# mcp23017_L298.net
KiCad netlist of a schematic drawn in EAGLE
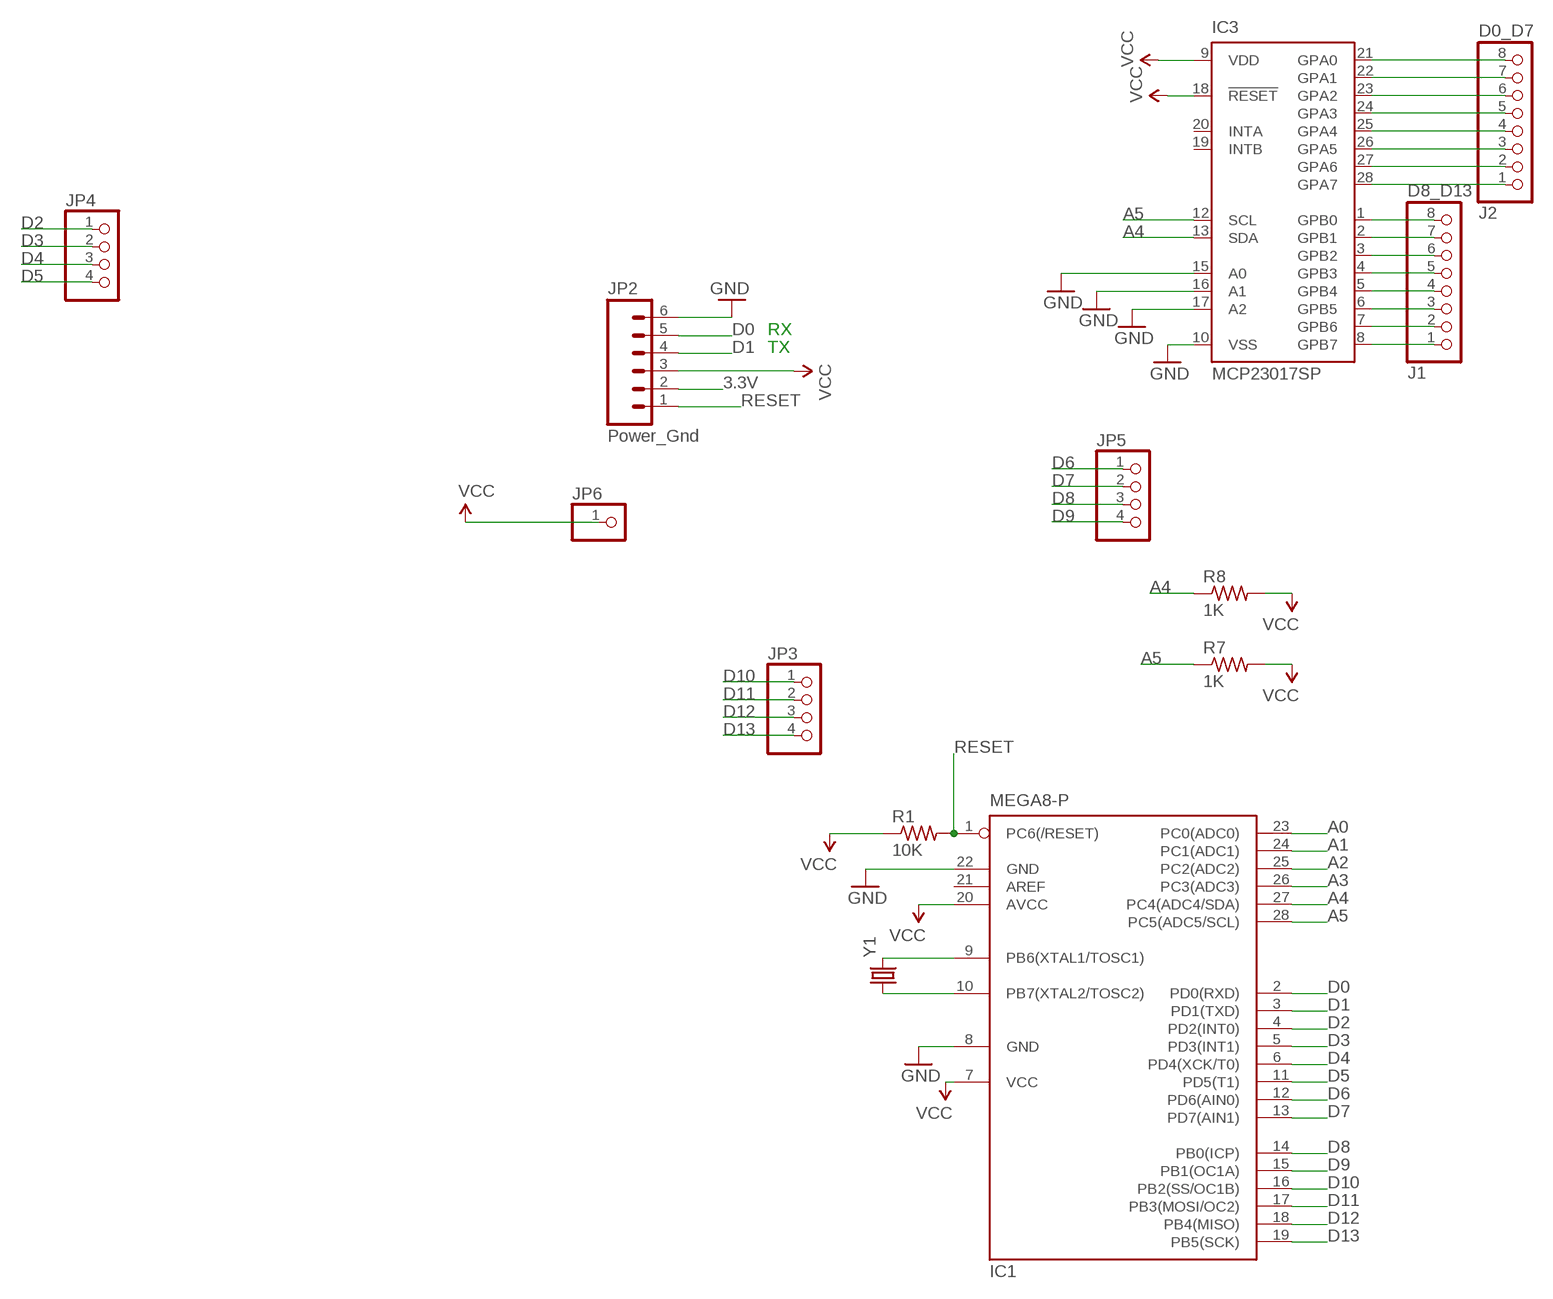
[diagram p0: schematic, sheet 1]

(export (version "E")
  (design (tool "Eeschema 10.0.6"))
  (components
    (comp (ref "IC1")
      (value "MEGA8-P")
      (footprint "eagle-import:DIL28-3")
      (libsource (lib "eagle-import") (part "MEGA8-P"))
    )
    (comp (ref "IC3")
      (value "MCP23017SP")
      (footprint "eagle-import:DIL28-3")
      (fields (field (name "MF") "MICROCHIP") (field (name "MPN") "MCP23017-E/SP"))
      (libsource (lib "eagle-import") (part "MCP23017SP"))
    )
    (comp (ref "J1")
      (value "D8_D13")
      (footprint "eagle-import:1X08")
      (libsource (lib "eagle-import") (part "PINHD-1X8"))
    )
    (comp (ref "J2")
      (value "D0_D7")
      (footprint "eagle-import:1X08")
      (libsource (lib "eagle-import") (part "PINHD-1X8"))
    )
    (comp (ref "JP2")
      (value "Power_Gnd")
      (footprint "eagle-import:1X06")
      (libsource (lib "eagle-import") (part "M06SIP"))
    )
    (comp (ref "JP3")
      (value "PINHD-1X4")
      (footprint "eagle-import:1X04")
      (libsource (lib "eagle-import") (part "PINHD-1X4"))
    )
    (comp (ref "JP4")
      (value "PINHD-1X4")
      (footprint "eagle-import:1X04")
      (libsource (lib "eagle-import") (part "PINHD-1X4"))
    )
    (comp (ref "JP5")
      (value "PINHD-1X4")
      (footprint "eagle-import:1X04")
      (libsource (lib "eagle-import") (part "PINHD-1X4"))
    )
    (comp (ref "JP6")
      (value "PINHD-1X1")
      (footprint "eagle-import:1X01")
      (libsource (lib "eagle-import") (part "PINHD-1X1"))
    )
    (comp (ref "R1")
      (value "10K")
      (footprint "eagle-import:0207_10")
      (libsource (lib "eagle-import") (part "R-US_0207/10"))
    )
    (comp (ref "R7")
      (value "1K")
      (footprint "eagle-import:0207_10")
      (libsource (lib "eagle-import") (part "R-US_0207/10"))
    )
    (comp (ref "R8")
      (value "1K")
      (footprint "eagle-import:0207_10")
      (libsource (lib "eagle-import") (part "R-US_0207/10"))
    )
    (comp (ref "Y1")
      (value "CRYSTALHC49US")
      (footprint "eagle-import:HC49US")
      (libsource (lib "eagle-import") (part "CRYSTALHC49US"))
    )
  )
  (nets
    (net (code "1") (name "/3.3V") (class "Default")
      (node (ref "JP2") (pin "2") (pinfunction "2_2") (pintype "passive"))
    )
    (net (code "2") (name "/A0") (class "Default")
      (node (ref "IC1") (pin "23") (pinfunction "PC0(ADC0)_23") (pintype "bidirectional"))
    )
    (net (code "3") (name "/A1") (class "Default")
      (node (ref "IC1") (pin "24") (pinfunction "PC1(ADC1)_24") (pintype "bidirectional"))
    )
    (net (code "4") (name "/A2") (class "Default")
      (node (ref "IC1") (pin "25") (pinfunction "PC2(ADC2)_25") (pintype "bidirectional"))
    )
    (net (code "5") (name "/A3") (class "Default")
      (node (ref "IC1") (pin "26") (pinfunction "PC3(ADC3)_26") (pintype "bidirectional"))
    )
    (net (code "6") (name "/A4") (class "Default")
      (node (ref "IC1") (pin "27") (pinfunction "PC4(ADC4/SDA)_27") (pintype "bidirectional"))
      (node (ref "IC3") (pin "13") (pinfunction "SDA_13") (pintype "bidirectional"))
      (node (ref "R8") (pin "1") (pinfunction "1_1") (pintype "passive"))
    )
    (net (code "7") (name "/A5") (class "Default")
      (node (ref "IC1") (pin "28") (pinfunction "PC5(ADC5/SCL)_28") (pintype "bidirectional"))
      (node (ref "IC3") (pin "12") (pinfunction "SCL_12") (pintype "input"))
      (node (ref "R7") (pin "1") (pinfunction "1_1") (pintype "passive"))
    )
    (net (code "8") (name "/D0") (class "Default")
      (node (ref "IC1") (pin "2") (pinfunction "PD0(RXD)_2") (pintype "bidirectional"))
      (node (ref "JP2") (pin "5") (pinfunction "5_5") (pintype "passive"))
    )
    (net (code "9") (name "/D1") (class "Default")
      (node (ref "IC1") (pin "3") (pinfunction "PD1(TXD)_3") (pintype "bidirectional"))
      (node (ref "JP2") (pin "4") (pinfunction "4_4") (pintype "passive"))
    )
    (net (code "10") (name "/D2") (class "Default")
      (node (ref "IC1") (pin "4") (pinfunction "PD2(INT0)_4") (pintype "bidirectional"))
      (node (ref "JP4") (pin "1") (pinfunction "1_1") (pintype "passive"))
    )
    (net (code "11") (name "/D3") (class "Default")
      (node (ref "IC1") (pin "5") (pinfunction "PD3(INT1)_5") (pintype "bidirectional"))
      (node (ref "JP4") (pin "2") (pinfunction "2_2") (pintype "passive"))
    )
    (net (code "12") (name "/D4") (class "Default")
      (node (ref "IC1") (pin "6") (pinfunction "PD4(XCK/T0)_6") (pintype "bidirectional"))
      (node (ref "JP4") (pin "3") (pinfunction "3_3") (pintype "passive"))
    )
    (net (code "13") (name "/D5") (class "Default")
      (node (ref "IC1") (pin "11") (pinfunction "PD5(T1)_11") (pintype "bidirectional"))
      (node (ref "JP4") (pin "4") (pinfunction "4_4") (pintype "passive"))
    )
    (net (code "14") (name "/D6") (class "Default")
      (node (ref "IC1") (pin "12") (pinfunction "PD6(AIN0)_12") (pintype "bidirectional"))
      (node (ref "JP5") (pin "1") (pinfunction "1_1") (pintype "passive"))
    )
    (net (code "15") (name "/D7") (class "Default")
      (node (ref "IC1") (pin "13") (pinfunction "PD7(AIN1)_13") (pintype "bidirectional"))
      (node (ref "JP5") (pin "2") (pinfunction "2_2") (pintype "passive"))
    )
    (net (code "16") (name "/D8") (class "Default")
      (node (ref "IC1") (pin "14") (pinfunction "PB0(ICP)_14") (pintype "bidirectional"))
      (node (ref "JP5") (pin "3") (pinfunction "3_3") (pintype "passive"))
    )
    (net (code "17") (name "/D9") (class "Default")
      (node (ref "IC1") (pin "15") (pinfunction "PB1(OC1A)_15") (pintype "bidirectional"))
      (node (ref "JP5") (pin "4") (pinfunction "4_4") (pintype "passive"))
    )
    (net (code "18") (name "/D10") (class "Default")
      (node (ref "IC1") (pin "16") (pinfunction "PB2(SS/OC1B)_16") (pintype "bidirectional"))
      (node (ref "JP3") (pin "1") (pinfunction "1_1") (pintype "passive"))
    )
    (net (code "19") (name "/D11") (class "Default")
      (node (ref "IC1") (pin "17") (pinfunction "PB3(MOSI/OC2)_17") (pintype "bidirectional"))
      (node (ref "JP3") (pin "2") (pinfunction "2_2") (pintype "passive"))
    )
    (net (code "20") (name "/D12") (class "Default")
      (node (ref "IC1") (pin "18") (pinfunction "PB4(MISO)_18") (pintype "bidirectional"))
      (node (ref "JP3") (pin "3") (pinfunction "3_3") (pintype "passive"))
    )
    (net (code "21") (name "/D13") (class "Default")
      (node (ref "IC1") (pin "19") (pinfunction "PB5(SCK)_19") (pintype "bidirectional"))
      (node (ref "JP3") (pin "4") (pinfunction "4_4") (pintype "passive"))
    )
    (net (code "22") (name "/RESET") (class "Default")
      (node (ref "IC1") (pin "1") (pinfunction "PC6(/RESET)_1") (pintype "bidirectional"))
      (node (ref "JP2") (pin "1") (pinfunction "1_1") (pintype "passive"))
      (node (ref "R1") (pin "2") (pinfunction "2_2") (pintype "passive"))
    )
    (net (code "23") (name "GND") (class "Default")
      (node (ref "IC1") (pin "22") (pinfunction "GND_22") (pintype "power_in"))
      (node (ref "IC1") (pin "8") (pinfunction "GND_8") (pintype "power_in"))
      (node (ref "IC3") (pin "10") (pinfunction "VSS_10") (pintype "power_in"))
      (node (ref "IC3") (pin "15") (pinfunction "A0_15") (pintype "input"))
      (node (ref "IC3") (pin "16") (pinfunction "A1_16") (pintype "input"))
      (node (ref "IC3") (pin "17") (pinfunction "A2_17") (pintype "input"))
      (node (ref "JP2") (pin "6") (pinfunction "6_6") (pintype "passive"))
    )
    (net (code "24") (name "Net-(IC1-PB6(XTAL1{slash}TOSC1))") (class "Default")
      (node (ref "IC1") (pin "9") (pinfunction "PB6(XTAL1/TOSC1)_9") (pintype "bidirectional"))
      (node (ref "Y1") (pin "2") (pinfunction "2_2") (pintype "passive"))
    )
    (net (code "25") (name "Net-(IC1-PB7(XTAL2{slash}TOSC2))") (class "Default")
      (node (ref "IC1") (pin "10") (pinfunction "PB7(XTAL2/TOSC2)_10") (pintype "bidirectional"))
      (node (ref "Y1") (pin "1") (pinfunction "1_1") (pintype "passive"))
    )
    (net (code "26") (name "Net-(IC3-GPA0)") (class "Default")
      (node (ref "IC3") (pin "21") (pinfunction "GPA0_21") (pintype "bidirectional"))
      (node (ref "J2") (pin "8") (pinfunction "8_8") (pintype "passive"))
    )
    (net (code "27") (name "Net-(IC3-GPA1)") (class "Default")
      (node (ref "IC3") (pin "22") (pinfunction "GPA1_22") (pintype "bidirectional"))
      (node (ref "J2") (pin "7") (pinfunction "7_7") (pintype "passive"))
    )
    (net (code "28") (name "Net-(IC3-GPA2)") (class "Default")
      (node (ref "IC3") (pin "23") (pinfunction "GPA2_23") (pintype "bidirectional"))
      (node (ref "J2") (pin "6") (pinfunction "6_6") (pintype "passive"))
    )
    (net (code "29") (name "Net-(IC3-GPA3)") (class "Default")
      (node (ref "IC3") (pin "24") (pinfunction "GPA3_24") (pintype "bidirectional"))
      (node (ref "J2") (pin "5") (pinfunction "5_5") (pintype "passive"))
    )
    (net (code "30") (name "Net-(IC3-GPA4)") (class "Default")
      (node (ref "IC3") (pin "25") (pinfunction "GPA4_25") (pintype "bidirectional"))
      (node (ref "J2") (pin "4") (pinfunction "4_4") (pintype "passive"))
    )
    (net (code "31") (name "Net-(IC3-GPA5)") (class "Default")
      (node (ref "IC3") (pin "26") (pinfunction "GPA5_26") (pintype "bidirectional"))
      (node (ref "J2") (pin "3") (pinfunction "3_3") (pintype "passive"))
    )
    (net (code "32") (name "Net-(IC3-GPA6)") (class "Default")
      (node (ref "IC3") (pin "27") (pinfunction "GPA6_27") (pintype "bidirectional"))
      (node (ref "J2") (pin "2") (pinfunction "2_2") (pintype "passive"))
    )
    (net (code "33") (name "Net-(IC3-GPA7)") (class "Default")
      (node (ref "IC3") (pin "28") (pinfunction "GPA7_28") (pintype "bidirectional"))
      (node (ref "J2") (pin "1") (pinfunction "1_1") (pintype "passive"))
    )
    (net (code "34") (name "Net-(IC3-GPB0)") (class "Default")
      (node (ref "IC3") (pin "1") (pinfunction "GPB0_1") (pintype "bidirectional"))
      (node (ref "J1") (pin "8") (pinfunction "8_8") (pintype "passive"))
    )
    (net (code "35") (name "Net-(IC3-GPB1)") (class "Default")
      (node (ref "IC3") (pin "2") (pinfunction "GPB1_2") (pintype "bidirectional"))
      (node (ref "J1") (pin "7") (pinfunction "7_7") (pintype "passive"))
    )
    (net (code "36") (name "Net-(IC3-GPB2)") (class "Default")
      (node (ref "IC3") (pin "3") (pinfunction "GPB2_3") (pintype "bidirectional"))
      (node (ref "J1") (pin "6") (pinfunction "6_6") (pintype "passive"))
    )
    (net (code "37") (name "Net-(IC3-GPB3)") (class "Default")
      (node (ref "IC3") (pin "4") (pinfunction "GPB3_4") (pintype "bidirectional"))
      (node (ref "J1") (pin "5") (pinfunction "5_5") (pintype "passive"))
    )
    (net (code "38") (name "Net-(IC3-GPB4)") (class "Default")
      (node (ref "IC3") (pin "5") (pinfunction "GPB4_5") (pintype "bidirectional"))
      (node (ref "J1") (pin "4") (pinfunction "4_4") (pintype "passive"))
    )
    (net (code "39") (name "Net-(IC3-GPB5)") (class "Default")
      (node (ref "IC3") (pin "6") (pinfunction "GPB5_6") (pintype "bidirectional"))
      (node (ref "J1") (pin "3") (pinfunction "3_3") (pintype "passive"))
    )
    (net (code "40") (name "Net-(IC3-GPB6)") (class "Default")
      (node (ref "IC3") (pin "7") (pinfunction "GPB6_7") (pintype "bidirectional"))
      (node (ref "J1") (pin "2") (pinfunction "2_2") (pintype "passive"))
    )
    (net (code "41") (name "Net-(IC3-GPB7)") (class "Default")
      (node (ref "IC3") (pin "8") (pinfunction "GPB7_8") (pintype "bidirectional"))
      (node (ref "J1") (pin "1") (pinfunction "1_1") (pintype "passive"))
    )
    (net (code "42") (name "VCC") (class "Default")
      (node (ref "IC1") (pin "20") (pinfunction "AVCC_20") (pintype "power_in"))
      (node (ref "IC1") (pin "7") (pinfunction "VCC_7") (pintype "power_in"))
      (node (ref "IC3") (pin "18") (pinfunction "~{RESET}_18") (pintype "input"))
      (node (ref "IC3") (pin "9") (pinfunction "VDD_9") (pintype "power_in"))
      (node (ref "JP2") (pin "3") (pinfunction "3_3") (pintype "passive"))
      (node (ref "JP6") (pin "1") (pinfunction "1_1") (pintype "passive"))
      (node (ref "R1") (pin "1") (pinfunction "1_1") (pintype "passive"))
      (node (ref "R7") (pin "2") (pinfunction "2_2") (pintype "passive"))
      (node (ref "R8") (pin "2") (pinfunction "2_2") (pintype "passive"))
    )
    (net (code "43") (name "unconnected-(IC1-AREF-Pad21)") (class "Default")
      (node (ref "IC1") (pin "21") (pinfunction "AREF_21") (pintype "passive"))
    )
    (net (code "44") (name "unconnected-(IC3-INTA-Pad20)") (class "Default")
      (node (ref "IC3") (pin "20") (pinfunction "INTA_20") (pintype "output"))
    )
    (net (code "45") (name "unconnected-(IC3-INTB-Pad19)") (class "Default")
      (node (ref "IC3") (pin "19") (pinfunction "INTB_19") (pintype "output"))
    )
  )
)
